# SCH.net
KiCad netlist of a schematic drawn in EasyEDA
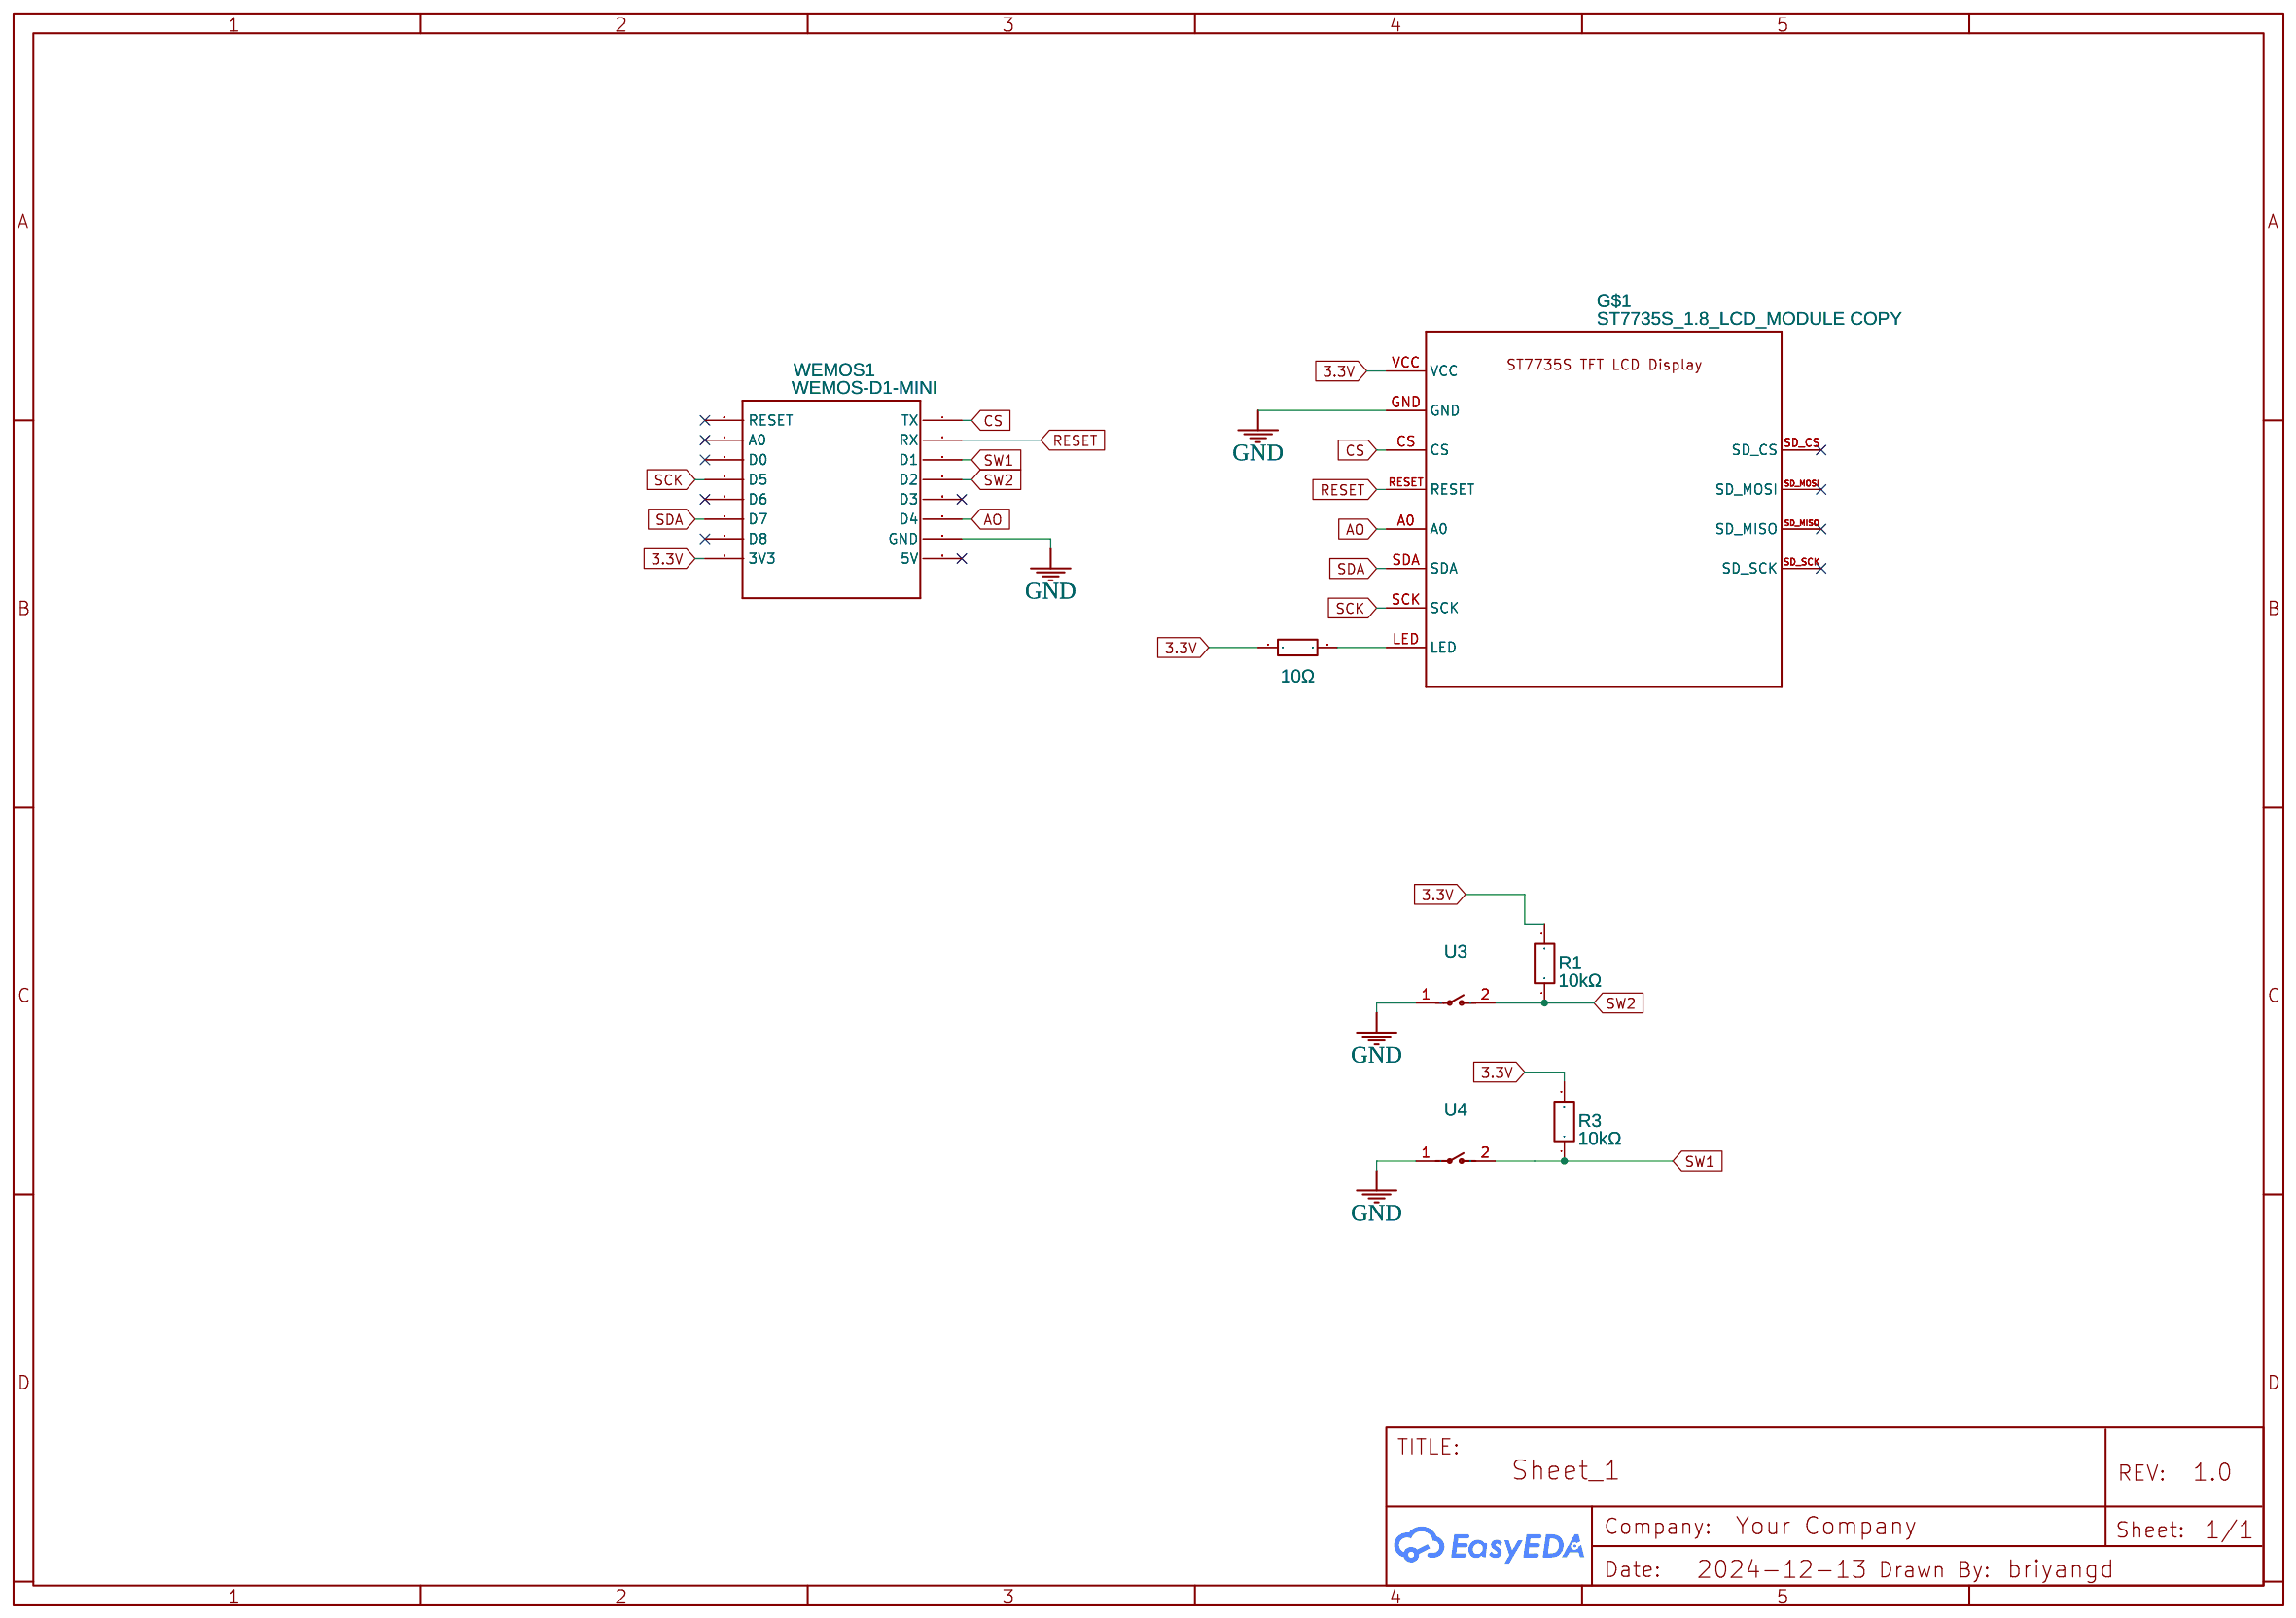
[diagram p0: schematic sheet]

(export (version "E")
  (design (tool "Eeschema 10.0.6"))
  (components
    (comp (ref "G$1")
      (value "ST7735S_1.8_LCD_MODULE COPY")
      (libsource (lib "") (part "ST7735S_1.8_LCD_MODULE COPY"))
    )
    (comp (ref "R1")
      (value "10kΩ")
      (fields
        (field (name "Manufacturer Part") "RN1/4W10KFT/BA1")
        (field (name "Manufacturer") "Tyohm(幸亚电阻)")
      )
      (libsource (lib "") (part "RN 1/4W 10K F T/B A1"))
    )
    (comp (ref "R2")
      (value "10Ω")
      (fields (field (name "Manufacturer Part") "KNP2W-10Ω±5% T") (field (name "Manufacturer") "CCO(千志电子)"))
      (libsource (lib "") (part "KNP2W-10Ω±5% T"))
    )
    (comp (ref "R3")
      (value "10kΩ")
      (fields
        (field (name "Manufacturer Part") "RN1/4W10KFT/BA1")
        (field (name "Manufacturer") "Tyohm(幸亚电阻)")
      )
      (libsource (lib "") (part "RN 1/4W 10K F T/B A1"))
    )
    (comp (ref "U3")
      (value "EVQ-11D05B")
      (fields (field (name "Manufacturer") "PANASONIC(松下)"))
      (libsource (lib "") (part "EVQ-11D05B"))
    )
    (comp (ref "U4")
      (value "EVQ-11D05B")
      (fields (field (name "Manufacturer") "PANASONIC(松下)"))
      (libsource (lib "") (part "EVQ-11D05B"))
    )
    (comp (ref "WEMOS1") (value "WEMOS-D1-MINI") (libsource (lib "") (part "WEMOS-D1-MINI")))
  )
  (nets
    (net (code "1") (name "3.3V") (class "Default")
      (node (ref "G$1") (pin "VCC") (pinfunction "VCC_VCC") (pintype "bidirectional"))
      (node (ref "R1") (pin "2") (pinfunction "2_2") (pintype "unspecified"))
      (node (ref "R2") (pin "1") (pinfunction "1_1") (pintype "unspecified"))
      (node (ref "R3") (pin "2") (pinfunction "2_2") (pintype "unspecified"))
      (node (ref "WEMOS1") (pin "3V3") (pinfunction "3V3_3V3") (pintype "bidirectional"))
    )
    (net (code "2") (name "AO") (class "Default")
      (node (ref "G$1") (pin "A0") (pinfunction "A0_A0") (pintype "bidirectional"))
      (node (ref "WEMOS1") (pin "D4") (pinfunction "D4_D4") (pintype "bidirectional"))
    )
    (net (code "3") (name "CS") (class "Default")
      (node (ref "G$1") (pin "CS") (pinfunction "CS_CS") (pintype "bidirectional"))
      (node (ref "WEMOS1") (pin "TX") (pinfunction "TX_TX") (pintype "bidirectional"))
    )
    (net (code "4") (name "GND") (class "Default")
      (node (ref "G$1") (pin "GND") (pinfunction "GND_GND") (pintype "bidirectional"))
      (node (ref "U3") (pin "1") (pinfunction "1_1") (pintype "unspecified"))
      (node (ref "U4") (pin "1") (pinfunction "1_1") (pintype "unspecified"))
      (node (ref "WEMOS1") (pin "GND") (pinfunction "GND_GND") (pintype "bidirectional"))
    )
    (net (code "5") (name "Net-(G$1-PadLED)") (class "Default")
      (node (ref "G$1") (pin "LED") (pinfunction "LED_LED") (pintype "bidirectional"))
      (node (ref "R2") (pin "2") (pinfunction "2_2") (pintype "unspecified"))
    )
    (net (code "6") (name "RESET") (class "Default")
      (node (ref "G$1") (pin "RESET") (pinfunction "RESET_RESET") (pintype "bidirectional"))
      (node (ref "WEMOS1") (pin "RX") (pinfunction "RX_RX") (pintype "bidirectional"))
    )
    (net (code "7") (name "SCK") (class "Default")
      (node (ref "G$1") (pin "SCK") (pinfunction "SCK_SCK") (pintype "bidirectional"))
      (node (ref "WEMOS1") (pin "D5") (pinfunction "D5_D5") (pintype "bidirectional"))
    )
    (net (code "8") (name "SDA") (class "Default")
      (node (ref "G$1") (pin "SDA") (pinfunction "SDA_SDA") (pintype "bidirectional"))
      (node (ref "WEMOS1") (pin "D7") (pinfunction "D7_D7") (pintype "bidirectional"))
    )
    (net (code "9") (name "SW1") (class "Default")
      (node (ref "R3") (pin "1") (pinfunction "1_1") (pintype "unspecified"))
      (node (ref "U4") (pin "2") (pinfunction "2_2") (pintype "unspecified"))
      (node (ref "WEMOS1") (pin "D1") (pinfunction "D1_D1") (pintype "bidirectional"))
    )
    (net (code "10") (name "SW2") (class "Default")
      (node (ref "R1") (pin "1") (pinfunction "1_1") (pintype "unspecified"))
      (node (ref "U3") (pin "2") (pinfunction "2_2") (pintype "unspecified"))
      (node (ref "WEMOS1") (pin "D2") (pinfunction "D2_D2") (pintype "bidirectional"))
    )
    (net (code "11") (name "unconnected-(G$1-PadSD_CS)") (class "Default")
      (node (ref "G$1") (pin "SD_CS") (pinfunction "SD_CS_SD_CS") (pintype "bidirectional+no_connect"))
    )
    (net (code "12") (name "unconnected-(G$1-PadSD_MISO)") (class "Default")
      (node (ref "G$1") (pin "SD_MISO") (pinfunction "SD_MISO_SD_MISO") (pintype "bidirectional+no_connect"))
    )
    (net (code "13") (name "unconnected-(G$1-PadSD_MOSI)") (class "Default")
      (node (ref "G$1") (pin "SD_MOSI") (pinfunction "SD_MOSI_SD_MOSI") (pintype "bidirectional+no_connect"))
    )
    (net (code "14") (name "unconnected-(G$1-PadSD_SCK)") (class "Default")
      (node (ref "G$1") (pin "SD_SCK") (pinfunction "SD_SCK_SD_SCK") (pintype "bidirectional+no_connect"))
    )
    (net (code "15") (name "unconnected-(WEMOS1-Pad5V)") (class "Default")
      (node (ref "WEMOS1") (pin "5V") (pinfunction "5V_5V") (pintype "bidirectional+no_connect"))
    )
    (net (code "16") (name "unconnected-(WEMOS1-PadA0)") (class "Default")
      (node (ref "WEMOS1") (pin "A0") (pinfunction "A0_A0") (pintype "bidirectional+no_connect"))
    )
    (net (code "17") (name "unconnected-(WEMOS1-PadD0)") (class "Default")
      (node (ref "WEMOS1") (pin "D0") (pinfunction "D0_D0") (pintype "bidirectional+no_connect"))
    )
    (net (code "18") (name "unconnected-(WEMOS1-PadD3)") (class "Default")
      (node (ref "WEMOS1") (pin "D3") (pinfunction "D3_D3") (pintype "bidirectional+no_connect"))
    )
    (net (code "19") (name "unconnected-(WEMOS1-PadD6)") (class "Default")
      (node (ref "WEMOS1") (pin "D6") (pinfunction "D6_D6") (pintype "bidirectional+no_connect"))
    )
    (net (code "20") (name "unconnected-(WEMOS1-PadD8)") (class "Default")
      (node (ref "WEMOS1") (pin "D8") (pinfunction "D8_D8") (pintype "bidirectional+no_connect"))
    )
    (net (code "21") (name "unconnected-(WEMOS1-PadRESET)") (class "Default")
      (node (ref "WEMOS1") (pin "RESET") (pinfunction "RESET_RESET") (pintype "bidirectional+no_connect"))
    )
  )
)
